# SCH_train-system-design_2026-06-14.net
KiCad netlist of a schematic drawn in EasyEDA
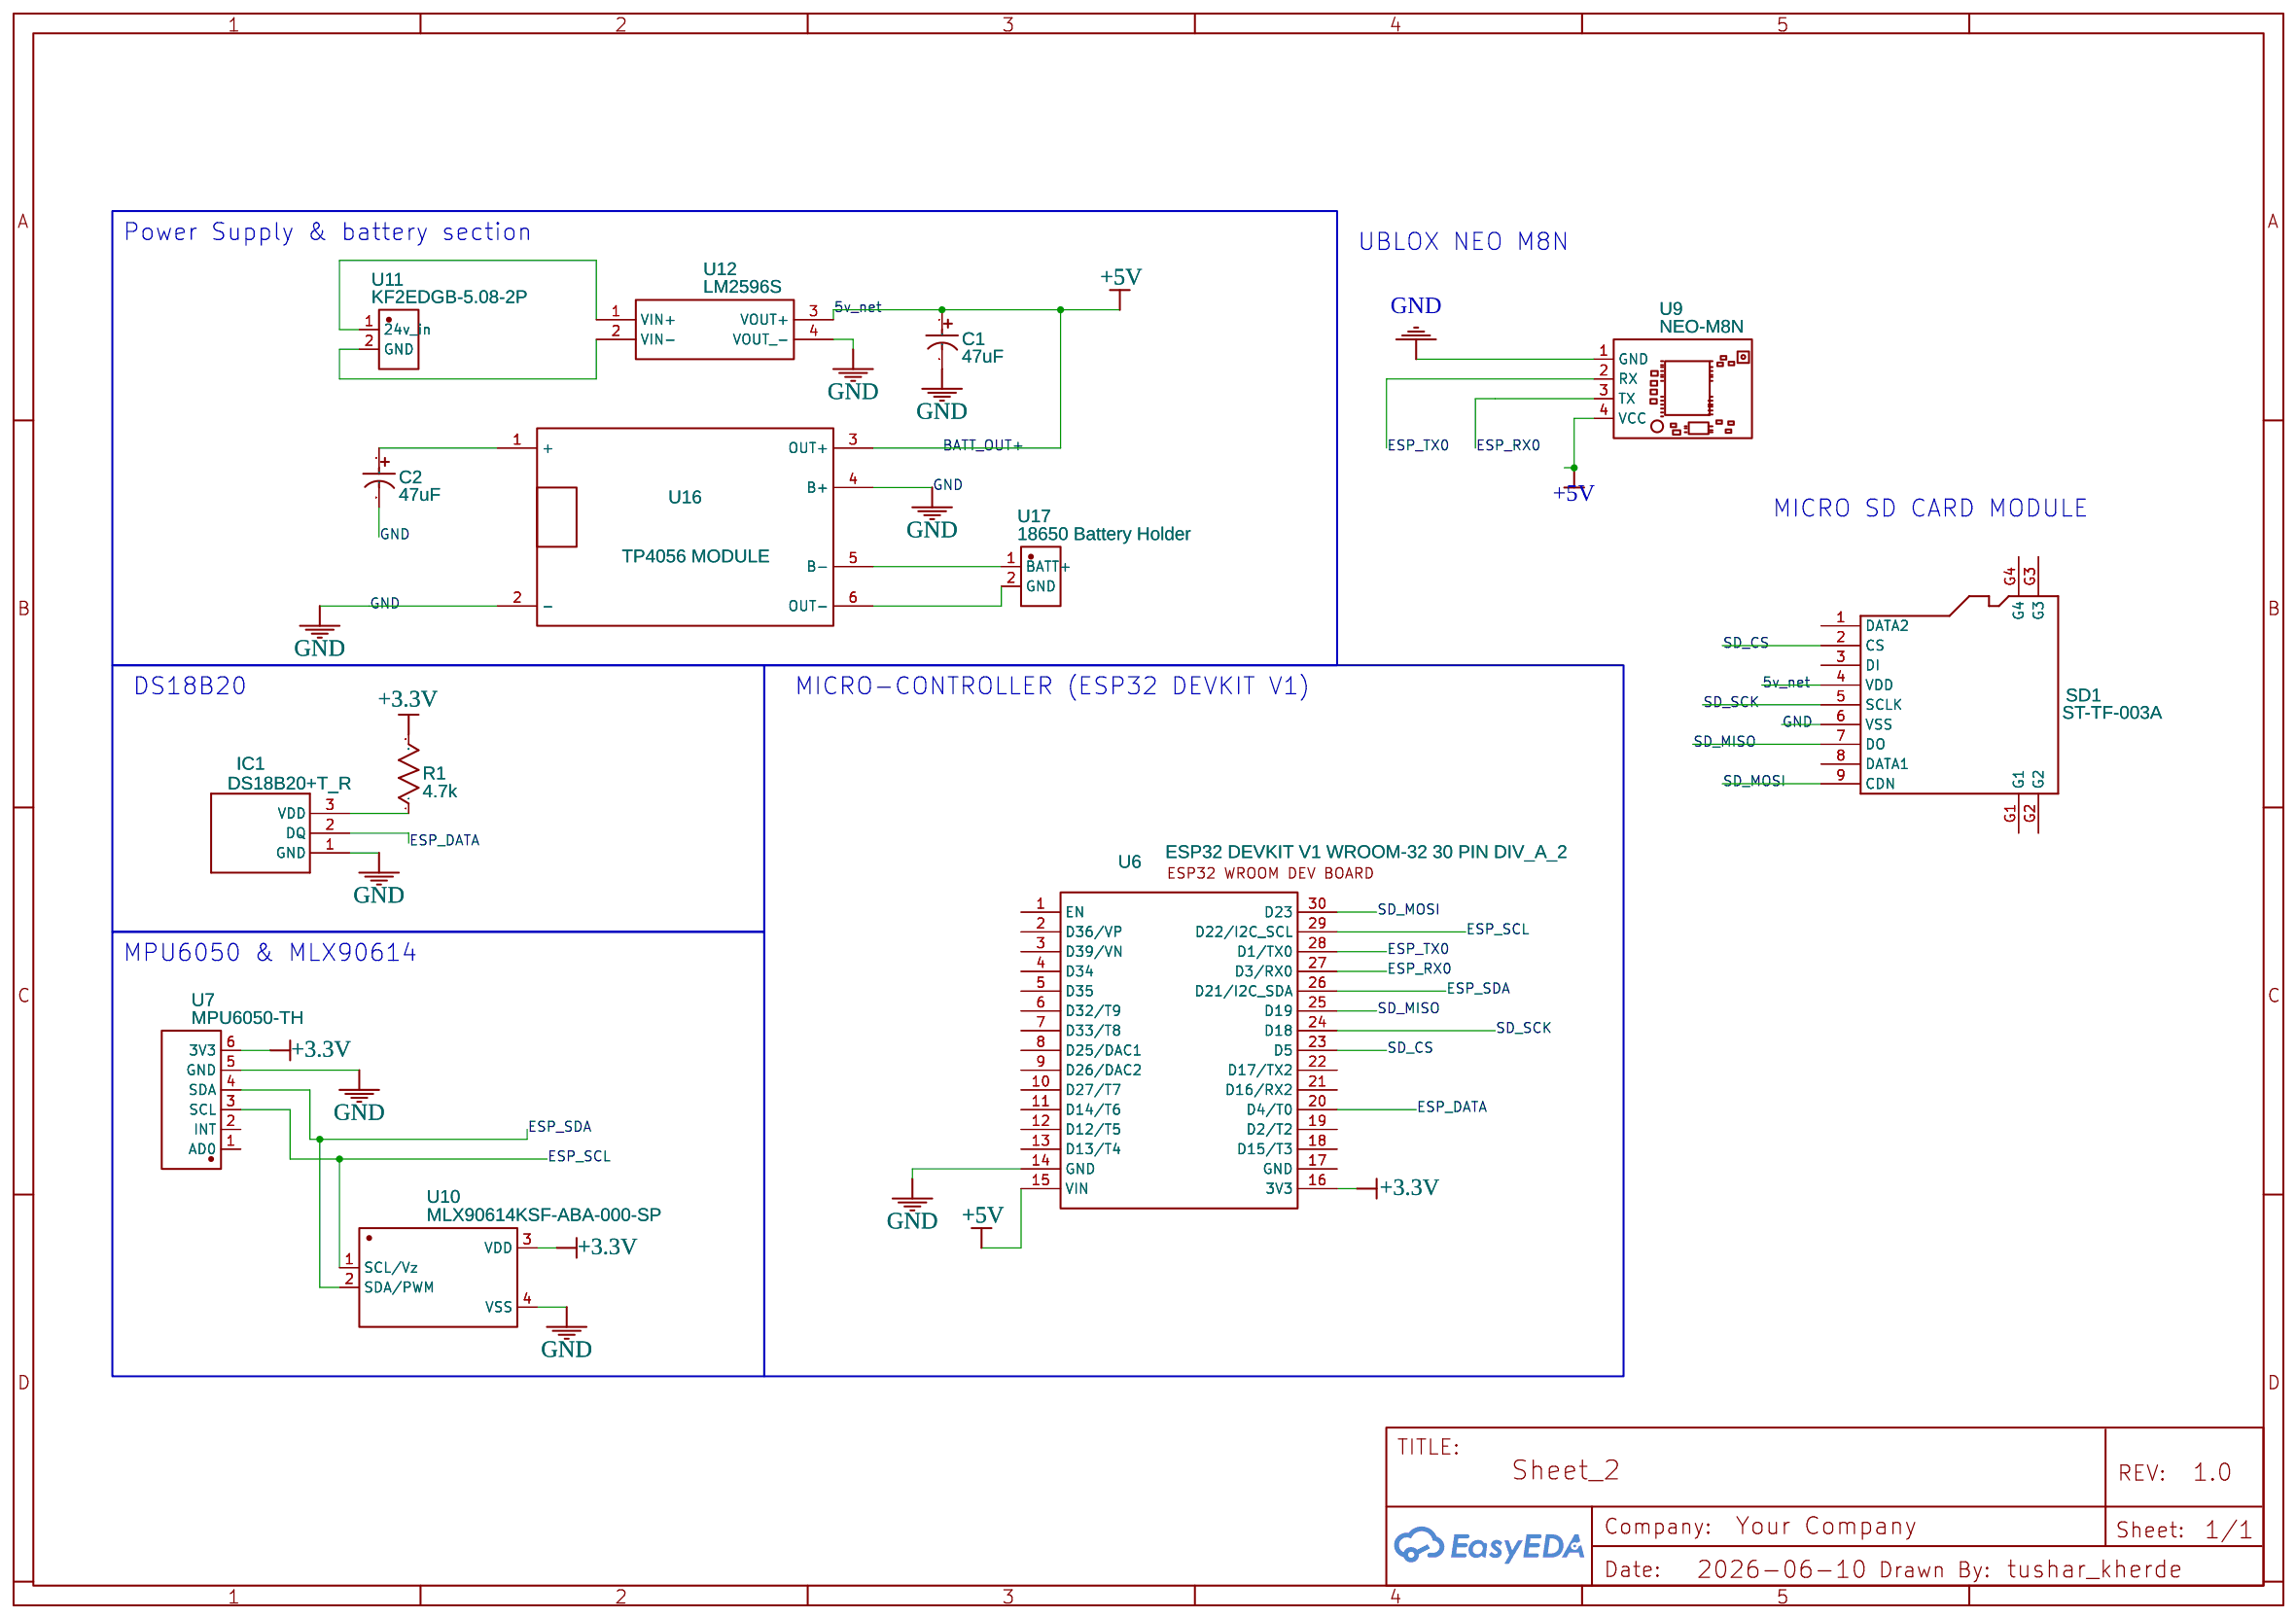
[diagram p0: schematic sheet]

(export (version "E")
  (design (tool "Eeschema 10.0.6"))
  (components
    (comp (ref "C1")
      (value "47uF")
      (fields
        (field (name "Manufacturer Part") "KM476M016D11RR0VH2FP0")
        (field (name "Manufacturer") "Chengx(承兴)")
      )
      (libsource (lib "") (part "47uF 16V Aluminum electrolytic capacitors"))
    )
    (comp (ref "C2")
      (value "47uF")
      (fields
        (field (name "Manufacturer Part") "KM476M016D11RR0VH2FP0")
        (field (name "Manufacturer") "Chengx(承兴)")
      )
      (libsource (lib "") (part "47uF 16V Aluminum electrolytic capacitors"))
    )
    (comp (ref "IC1") (value "DS18B20+T_R") (libsource (lib "") (part "DS18B20+T_R")))
    (comp (ref "R1") (value "4.7k") (libsource (lib "") (part "R_0603_US")))
    (comp (ref "SD1") (value "ST-TF-003A") (libsource (lib "") (part "ST-TF-003A")))
    (comp (ref "U6")
      (value "ESP32 DEVKIT V1 WROOM-32 30 PIN DIV_A_2")
      (libsource (lib "") (part "ESP32 DEVKIT V1 WROOM-32 30 PIN DIV_A_2"))
    )
    (comp (ref "U7") (value "MPU6050-TH") (libsource (lib "") (part "MPU6050-TH")))
    (comp (ref "U9") (value "NEO-M8N") (libsource (lib "") (part "NEO-M8N")))
    (comp (ref "U10")
      (value "MLX90614KSF-ABA-000-SP")
      (fields (field (name "Manufacturer") "Melexis(比利时迈来芯)"))
      (libsource (lib "") (part "MLX90614KSF-ABA-000-SP"))
    )
    (comp (ref "U11")
      (value "KF2EDGB-5.08-2P")
      (fields (field (name "Manufacturer") "KEFA(科发)"))
      (libsource (lib "") (part "KF2EDGB-5.08-2P"))
    )
    (comp (ref "U12")
      (value "LM2596S")
      (fields (field (name "Manufacturer Part") "LM2596S-DC-DC") (field (name "Manufacturer") "10Gtek"))
      (libsource (lib "") (part "LM2596S"))
    )
    (comp (ref "U16") (value "TP4056 MODULE") (libsource (lib "") (part "TP4056 MODULE")))
    (comp (ref "U17")
      (value "18650 Battery Holder")
      (fields
        (field (name "Manufacturer Part") "HMT-2.54-1*2PM")
        (field (name "Manufacturer") "HMTCONN(华明通)")
      )
      (libsource (lib "") (part "HMT-2.54-1*2PM"))
    )
  )
  (nets
    (net (code "1") (name "+3.3V") (class "Default")
      (node (ref "R1") (pin "2") (pinfunction "2_2") (pintype "unspecified"))
      (node (ref "U10") (pin "3") (pinfunction "VDD_3") (pintype "unspecified"))
      (node (ref "U6") (pin "16") (pinfunction "3V3_16") (pintype "unspecified"))
      (node (ref "U7") (pin "6") (pinfunction "3V3_6") (pintype "unspecified"))
    )
    (net (code "2") (name "+5V") (class "Default")
      (node (ref "C1") (pin "1") (pinfunction "1_1") (pintype "input"))
      (node (ref "SD1") (pin "4") (pinfunction "VDD_4") (pintype "unspecified"))
      (node (ref "U12") (pin "3") (pinfunction "VOUT+_3") (pintype "unspecified"))
      (node (ref "U16") (pin "3") (pinfunction "OUT+_3") (pintype "unspecified"))
      (node (ref "U6") (pin "15") (pinfunction "VIN_15") (pintype "unspecified"))
      (node (ref "U9") (pin "4") (pinfunction "VCC_4") (pintype "unspecified"))
    )
    (net (code "3") (name "/ESP_DATA") (class "Default")
      (node (ref "IC1") (pin "2") (pinfunction "DQ_2") (pintype "bidirectional"))
      (node (ref "U6") (pin "20") (pinfunction "D4/T0_20") (pintype "unspecified"))
    )
    (net (code "4") (name "/ESP_RX0") (class "Default")
      (node (ref "U6") (pin "27") (pinfunction "D3/RX0_27") (pintype "unspecified"))
      (node (ref "U9") (pin "3") (pinfunction "TX_3") (pintype "unspecified"))
    )
    (net (code "5") (name "/ESP_SCL") (class "Default")
      (node (ref "U10") (pin "1") (pinfunction "SCL/Vz_1") (pintype "unspecified"))
      (node (ref "U6") (pin "29") (pinfunction "D22/I2C_SCL_29") (pintype "unspecified"))
      (node (ref "U7") (pin "3") (pinfunction "SCL_3") (pintype "unspecified"))
    )
    (net (code "6") (name "/ESP_SDA") (class "Default")
      (node (ref "U10") (pin "2") (pinfunction "SDA/PWM_2") (pintype "unspecified"))
      (node (ref "U6") (pin "26") (pinfunction "D21/I2C_SDA_26") (pintype "unspecified"))
      (node (ref "U7") (pin "4") (pinfunction "SDA_4") (pintype "unspecified"))
    )
    (net (code "7") (name "/ESP_TX0") (class "Default")
      (node (ref "U6") (pin "28") (pinfunction "D1/TX0_28") (pintype "unspecified"))
      (node (ref "U9") (pin "2") (pinfunction "RX_2") (pintype "unspecified"))
    )
    (net (code "8") (name "/SD_CS") (class "Default")
      (node (ref "SD1") (pin "2") (pinfunction "CS_2") (pintype "unspecified"))
      (node (ref "U6") (pin "23") (pinfunction "D5_23") (pintype "unspecified"))
    )
    (net (code "9") (name "/SD_MISO") (class "Default")
      (node (ref "SD1") (pin "7") (pinfunction "DO_7") (pintype "unspecified"))
      (node (ref "U6") (pin "25") (pinfunction "D19_25") (pintype "unspecified"))
    )
    (net (code "10") (name "/SD_MOSI") (class "Default")
      (node (ref "SD1") (pin "9") (pinfunction "CDN_9") (pintype "unspecified"))
      (node (ref "U6") (pin "30") (pinfunction "D23_30") (pintype "unspecified"))
    )
    (net (code "11") (name "/SD_SCK") (class "Default")
      (node (ref "SD1") (pin "5") (pinfunction "SCLK_5") (pintype "unspecified"))
      (node (ref "U6") (pin "24") (pinfunction "D18_24") (pintype "unspecified"))
    )
    (net (code "12") (name "GND") (class "Default")
      (node (ref "C1") (pin "2") (pinfunction "2_2") (pintype "input"))
      (node (ref "C2") (pin "2") (pinfunction "2_2") (pintype "input"))
      (node (ref "IC1") (pin "1") (pinfunction "GND_1") (pintype "bidirectional"))
      (node (ref "SD1") (pin "6") (pinfunction "VSS_6") (pintype "unspecified"))
      (node (ref "U10") (pin "4") (pinfunction "VSS_4") (pintype "unspecified"))
      (node (ref "U12") (pin "4") (pinfunction "VOUT_-_4") (pintype "unspecified"))
      (node (ref "U16") (pin "2") (pinfunction "-_2") (pintype "unspecified"))
      (node (ref "U16") (pin "4") (pinfunction "B+_4") (pintype "unspecified"))
      (node (ref "U6") (pin "14") (pinfunction "GND_14") (pintype "unspecified"))
      (node (ref "U7") (pin "5") (pinfunction "GND_5") (pintype "unspecified"))
      (node (ref "U9") (pin "1") (pinfunction "GND_1") (pintype "unspecified"))
    )
    (net (code "13") (name "Net-(IC1-VDD)") (class "Default")
      (node (ref "IC1") (pin "3") (pinfunction "VDD_3") (pintype "bidirectional"))
      (node (ref "R1") (pin "1") (pinfunction "1_1") (pintype "unspecified"))
    )
    (net (code "14") (name "Net-(U11-24v_in)") (class "Default")
      (node (ref "U11") (pin "1") (pinfunction "24v_in_1") (pintype "unspecified"))
      (node (ref "U12") (pin "1") (pinfunction "VIN+_1") (pintype "unspecified"))
    )
    (net (code "15") (name "Net-(U11-GND)") (class "Default")
      (node (ref "U11") (pin "2") (pinfunction "GND_2") (pintype "unspecified"))
      (node (ref "U12") (pin "2") (pinfunction "VIN-_2") (pintype "unspecified"))
    )
    (net (code "16") (name "Net-(U16-+)") (class "Default")
      (node (ref "C2") (pin "1") (pinfunction "1_1") (pintype "input"))
      (node (ref "U16") (pin "1") (pinfunction "+_1") (pintype "unspecified"))
    )
    (net (code "17") (name "Net-(U16-B-)") (class "Default")
      (node (ref "U16") (pin "5") (pinfunction "B-_5") (pintype "unspecified"))
      (node (ref "U17") (pin "1") (pinfunction "BATT+_1") (pintype "unspecified"))
    )
    (net (code "18") (name "Net-(U16-OUT-)") (class "Default")
      (node (ref "U16") (pin "6") (pinfunction "OUT-_6") (pintype "unspecified"))
      (node (ref "U17") (pin "2") (pinfunction "GND_2") (pintype "unspecified"))
    )
    (net (code "19") (name "unconnected-(SD1-DATA1-Pad8)") (class "Default")
      (node (ref "SD1") (pin "8") (pinfunction "DATA1_8") (pintype "unspecified"))
    )
    (net (code "20") (name "unconnected-(SD1-DATA2-Pad1)") (class "Default")
      (node (ref "SD1") (pin "1") (pinfunction "DATA2_1") (pintype "unspecified"))
    )
    (net (code "21") (name "unconnected-(SD1-DI-Pad3)") (class "Default")
      (node (ref "SD1") (pin "3") (pinfunction "DI_3") (pintype "unspecified"))
    )
    (net (code "22") (name "unconnected-(SD1-PadG1)") (class "Default")
      (node (ref "SD1") (pin "G1") (pinfunction "G1_G1") (pintype "unspecified"))
    )
    (net (code "23") (name "unconnected-(SD1-PadG2)") (class "Default")
      (node (ref "SD1") (pin "G2") (pinfunction "G2_G2") (pintype "unspecified"))
    )
    (net (code "24") (name "unconnected-(SD1-PadG3)") (class "Default")
      (node (ref "SD1") (pin "G3") (pinfunction "G3_G3") (pintype "unspecified"))
    )
    (net (code "25") (name "unconnected-(SD1-PadG4)") (class "Default")
      (node (ref "SD1") (pin "G4") (pinfunction "G4_G4") (pintype "unspecified"))
    )
    (net (code "26") (name "unconnected-(U6-D2{slash}T2-Pad19)") (class "Default")
      (node (ref "U6") (pin "19") (pinfunction "D2/T2_19") (pintype "unspecified"))
    )
    (net (code "27") (name "unconnected-(U6-D12{slash}T5-Pad12)") (class "Default")
      (node (ref "U6") (pin "12") (pinfunction "D12/T5_12") (pintype "unspecified"))
    )
    (net (code "28") (name "unconnected-(U6-D13{slash}T4-Pad13)") (class "Default")
      (node (ref "U6") (pin "13") (pinfunction "D13/T4_13") (pintype "unspecified"))
    )
    (net (code "29") (name "unconnected-(U6-D14{slash}T6-Pad11)") (class "Default")
      (node (ref "U6") (pin "11") (pinfunction "D14/T6_11") (pintype "unspecified"))
    )
    (net (code "30") (name "unconnected-(U6-D15{slash}T3-Pad18)") (class "Default")
      (node (ref "U6") (pin "18") (pinfunction "D15/T3_18") (pintype "unspecified"))
    )
    (net (code "31") (name "unconnected-(U6-D16{slash}RX2-Pad21)") (class "Default")
      (node (ref "U6") (pin "21") (pinfunction "D16/RX2_21") (pintype "unspecified"))
    )
    (net (code "32") (name "unconnected-(U6-D17{slash}TX2-Pad22)") (class "Default")
      (node (ref "U6") (pin "22") (pinfunction "D17/TX2_22") (pintype "unspecified"))
    )
    (net (code "33") (name "unconnected-(U6-D25{slash}DAC1-Pad8)") (class "Default")
      (node (ref "U6") (pin "8") (pinfunction "D25/DAC1_8") (pintype "unspecified"))
    )
    (net (code "34") (name "unconnected-(U6-D26{slash}DAC2-Pad9)") (class "Default")
      (node (ref "U6") (pin "9") (pinfunction "D26/DAC2_9") (pintype "unspecified"))
    )
    (net (code "35") (name "unconnected-(U6-D27{slash}T7-Pad10)") (class "Default")
      (node (ref "U6") (pin "10") (pinfunction "D27/T7_10") (pintype "unspecified"))
    )
    (net (code "36") (name "unconnected-(U6-D32{slash}T9-Pad6)") (class "Default")
      (node (ref "U6") (pin "6") (pinfunction "D32/T9_6") (pintype "unspecified"))
    )
    (net (code "37") (name "unconnected-(U6-D33{slash}T8-Pad7)") (class "Default")
      (node (ref "U6") (pin "7") (pinfunction "D33/T8_7") (pintype "unspecified"))
    )
    (net (code "38") (name "unconnected-(U6-D34-Pad4)") (class "Default")
      (node (ref "U6") (pin "4") (pinfunction "D34_4") (pintype "unspecified"))
    )
    (net (code "39") (name "unconnected-(U6-D35-Pad5)") (class "Default")
      (node (ref "U6") (pin "5") (pinfunction "D35_5") (pintype "unspecified"))
    )
    (net (code "40") (name "unconnected-(U6-D36{slash}VP-Pad2)") (class "Default")
      (node (ref "U6") (pin "2") (pinfunction "D36/VP_2") (pintype "unspecified"))
    )
    (net (code "41") (name "unconnected-(U6-D39{slash}VN-Pad3)") (class "Default")
      (node (ref "U6") (pin "3") (pinfunction "D39/VN_3") (pintype "unspecified"))
    )
    (net (code "42") (name "unconnected-(U6-EN-Pad1)") (class "Default")
      (node (ref "U6") (pin "1") (pinfunction "EN_1") (pintype "unspecified"))
    )
    (net (code "43") (name "unconnected-(U6-GND-Pad17)") (class "Default")
      (node (ref "U6") (pin "17") (pinfunction "GND_17") (pintype "unspecified"))
    )
    (net (code "44") (name "unconnected-(U7-AD0-Pad1)") (class "Default")
      (node (ref "U7") (pin "1") (pinfunction "AD0_1") (pintype "unspecified"))
    )
    (net (code "45") (name "unconnected-(U7-INT-Pad2)") (class "Default")
      (node (ref "U7") (pin "2") (pinfunction "INT_2") (pintype "unspecified"))
    )
  )
)
